# In-Channels.net
KiCad netlist of a schematic drawn in Altium Designer
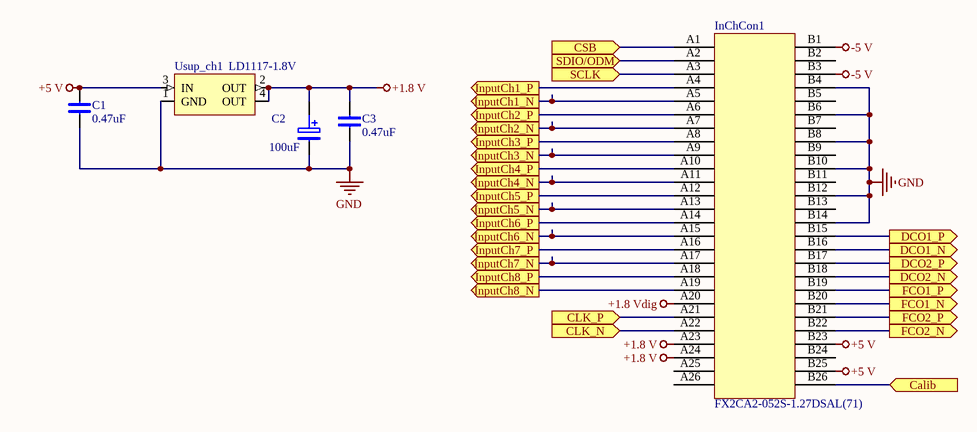
[diagram p0: In-Channels.SchDoc]

(export (version "E")
  (design (tool "Eeschema 10.0.6"))
  (components
    (comp (ref "C1") (value "0.47uF") (footprint "chip0603") (libsource (lib "*") (part "C")))
    (comp (ref "C2") (value "100uF") (footprint "CEL-SMD300") (libsource (lib "*") (part "C POL")))
    (comp (ref "C3") (value "0.47uF") (footprint "chip0603") (libsource (lib "*") (part "C")))
    (comp (ref "InChCon1")
      (value "FX2CA2-052S-1.27DSAL(71)")
      (footprint "FX2CA2-052S-1.27DSAL(71)")
      (libsource (lib "vDevice") (part "FX2CA2-052S-1.27DSAL(71)"))
    )
    (comp (ref "Usup_ch1")
      (value "LD1117-1.8V")
      (footprint "TO-252")
      (libsource (lib "vAnalog") (part "NCP1117-3.3V"))
    )
  )
  (nets
    (net (code "1") (name "+1.8 V") (class "Default")
      (node (ref "C2") (pin "+") (pinfunction "+_+") (pintype "passive"))
      (node (ref "C3") (pin "1") (pinfunction "1_1") (pintype "passive"))
      (node (ref "InChCon1") (pin "A23") (pinfunction "A23_A23") (pintype "passive"))
      (node (ref "InChCon1") (pin "A24") (pinfunction "A24_A24") (pintype "passive"))
      (node (ref "Usup_ch1") (pin "2") (pinfunction "OUT_2") (pintype "output"))
      (node (ref "Usup_ch1") (pin "4") (pinfunction "OUT_4") (pintype "passive"))
    )
    (net (code "2") (name "+1.8 Vdig") (class "Default")
      (node (ref "InChCon1") (pin "A20") (pinfunction "20_A20") (pintype "passive"))
    )
    (net (code "3") (name "+5 V") (class "Default")
      (node (ref "C1") (pin "1") (pinfunction "1_1") (pintype "passive"))
      (node (ref "InChCon1") (pin "B23") (pinfunction "B23_B23") (pintype "passive"))
      (node (ref "InChCon1") (pin "B25") (pinfunction "B25_B25") (pintype "passive"))
      (node (ref "Usup_ch1") (pin "3") (pinfunction "IN_3") (pintype "input"))
    )
    (net (code "4") (name "-5 V") (class "Default")
      (node (ref "InChCon1") (pin "B1") (pinfunction "1_B1") (pintype "passive"))
      (node (ref "InChCon1") (pin "B3") (pinfunction "3_B3") (pintype "passive"))
    )
    (net (code "5") (name "/CLK_N") (class "Default")
      (node (ref "InChCon1") (pin "A22") (pinfunction "A22_A22") (pintype "passive"))
    )
    (net (code "6") (name "/CLK_P") (class "Default")
      (node (ref "InChCon1") (pin "A21") (pinfunction "A21_A21") (pintype "passive"))
    )
    (net (code "7") (name "/CSB") (class "Default")
      (node (ref "InChCon1") (pin "A1") (pinfunction "1_A1") (pintype "passive"))
    )
    (net (code "8") (name "/Calib") (class "Default")
      (node (ref "InChCon1") (pin "B26") (pinfunction "B26_B26") (pintype "passive"))
    )
    (net (code "9") (name "/DCO1_N") (class "Default")
      (node (ref "InChCon1") (pin "B16") (pinfunction "16_B16") (pintype "passive"))
    )
    (net (code "10") (name "/DCO1_P") (class "Default")
      (node (ref "InChCon1") (pin "B15") (pinfunction "15_B15") (pintype "passive"))
    )
    (net (code "11") (name "/DCO2_N") (class "Default")
      (node (ref "InChCon1") (pin "B18") (pinfunction "18_B18") (pintype "passive"))
    )
    (net (code "12") (name "/DCO2_P") (class "Default")
      (node (ref "InChCon1") (pin "B17") (pinfunction "17_B17") (pintype "passive"))
    )
    (net (code "13") (name "/FCO1_N") (class "Default")
      (node (ref "InChCon1") (pin "B20") (pinfunction "20_B20") (pintype "passive"))
    )
    (net (code "14") (name "/FCO1_P") (class "Default")
      (node (ref "InChCon1") (pin "B19") (pinfunction "19_B19") (pintype "passive"))
    )
    (net (code "15") (name "/FCO2_N") (class "Default")
      (node (ref "InChCon1") (pin "B22") (pinfunction "B22_B22") (pintype "passive"))
    )
    (net (code "16") (name "/FCO2_P") (class "Default")
      (node (ref "InChCon1") (pin "B21") (pinfunction "B21_B21") (pintype "passive"))
    )
    (net (code "17") (name "/InputCh1_N") (class "Default")
      (node (ref "InChCon1") (pin "A5") (pinfunction "5_A5") (pintype "passive"))
    )
    (net (code "18") (name "/InputCh1_P") (class "Default")
      (node (ref "InChCon1") (pin "A4") (pinfunction "4_A4") (pintype "passive"))
    )
    (net (code "19") (name "/InputCh2_N") (class "Default")
      (node (ref "InChCon1") (pin "A7") (pinfunction "7_A7") (pintype "passive"))
    )
    (net (code "20") (name "/InputCh2_P") (class "Default")
      (node (ref "InChCon1") (pin "A6") (pinfunction "6_A6") (pintype "passive"))
    )
    (net (code "21") (name "/InputCh3_N") (class "Default")
      (node (ref "InChCon1") (pin "A9") (pinfunction "9_A9") (pintype "passive"))
    )
    (net (code "22") (name "/InputCh3_P") (class "Default")
      (node (ref "InChCon1") (pin "A8") (pinfunction "8_A8") (pintype "passive"))
    )
    (net (code "23") (name "/InputCh4_N") (class "Default")
      (node (ref "InChCon1") (pin "A11") (pinfunction "11_A11") (pintype "passive"))
    )
    (net (code "24") (name "/InputCh4_P") (class "Default")
      (node (ref "InChCon1") (pin "A10") (pinfunction "10_A10") (pintype "passive"))
    )
    (net (code "25") (name "/InputCh5_N") (class "Default")
      (node (ref "InChCon1") (pin "A13") (pinfunction "13_A13") (pintype "passive"))
    )
    (net (code "26") (name "/InputCh5_P") (class "Default")
      (node (ref "InChCon1") (pin "A12") (pinfunction "12_A12") (pintype "passive"))
    )
    (net (code "27") (name "/InputCh6_N") (class "Default")
      (node (ref "InChCon1") (pin "A15") (pinfunction "15_A15") (pintype "passive"))
    )
    (net (code "28") (name "/InputCh6_P") (class "Default")
      (node (ref "InChCon1") (pin "A14") (pinfunction "14_A14") (pintype "passive"))
    )
    (net (code "29") (name "/InputCh7_N") (class "Default")
      (node (ref "InChCon1") (pin "A17") (pinfunction "17_A17") (pintype "passive"))
    )
    (net (code "30") (name "/InputCh7_P") (class "Default")
      (node (ref "InChCon1") (pin "A16") (pinfunction "16_A16") (pintype "passive"))
    )
    (net (code "31") (name "/InputCh8_N") (class "Default")
      (node (ref "InChCon1") (pin "A19") (pinfunction "19_A19") (pintype "passive"))
    )
    (net (code "32") (name "/InputCh8_P") (class "Default")
      (node (ref "InChCon1") (pin "A18") (pinfunction "18_A18") (pintype "passive"))
    )
    (net (code "33") (name "/SCLK") (class "Default")
      (node (ref "InChCon1") (pin "A3") (pinfunction "3_A3") (pintype "passive"))
    )
    (net (code "34") (name "/SDIO{slash}ODM") (class "Default")
      (node (ref "InChCon1") (pin "A2") (pinfunction "2_A2") (pintype "passive"))
    )
    (net (code "35") (name "GND") (class "Default")
      (node (ref "C1") (pin "2") (pinfunction "2_2") (pintype "passive"))
      (node (ref "C2") (pin "-") (pinfunction "-_-") (pintype "passive"))
      (node (ref "C3") (pin "2") (pinfunction "2_2") (pintype "passive"))
      (node (ref "InChCon1") (pin "B10") (pinfunction "10_B10") (pintype "passive"))
      (node (ref "InChCon1") (pin "B12") (pinfunction "12_B12") (pintype "passive"))
      (node (ref "InChCon1") (pin "B14") (pinfunction "14_B14") (pintype "passive"))
      (node (ref "InChCon1") (pin "B4") (pinfunction "4_B4") (pintype "passive"))
      (node (ref "InChCon1") (pin "B6") (pinfunction "6_B6") (pintype "passive"))
      (node (ref "InChCon1") (pin "B8") (pinfunction "8_B8") (pintype "passive"))
      (node (ref "Usup_ch1") (pin "1") (pinfunction "GND_1") (pintype "power_in"))
    )
    (net (code "36") (name "unconnected-(InChCon1-2-PadB2)") (class "Default")
      (node (ref "InChCon1") (pin "B2") (pinfunction "2_B2") (pintype "passive"))
    )
    (net (code "37") (name "unconnected-(InChCon1-5-PadB5)") (class "Default")
      (node (ref "InChCon1") (pin "B5") (pinfunction "5_B5") (pintype "passive"))
    )
    (net (code "38") (name "unconnected-(InChCon1-7-PadB7)") (class "Default")
      (node (ref "InChCon1") (pin "B7") (pinfunction "7_B7") (pintype "passive"))
    )
    (net (code "39") (name "unconnected-(InChCon1-9-PadB9)") (class "Default")
      (node (ref "InChCon1") (pin "B9") (pinfunction "9_B9") (pintype "passive"))
    )
    (net (code "40") (name "unconnected-(InChCon1-11-PadB11)") (class "Default")
      (node (ref "InChCon1") (pin "B11") (pinfunction "11_B11") (pintype "passive"))
    )
    (net (code "41") (name "unconnected-(InChCon1-13-PadB13)") (class "Default")
      (node (ref "InChCon1") (pin "B13") (pinfunction "13_B13") (pintype "passive"))
    )
    (net (code "42") (name "unconnected-(InChCon1-PadA25)") (class "Default")
      (node (ref "InChCon1") (pin "A25") (pinfunction "A25_A25") (pintype "passive"))
    )
    (net (code "43") (name "unconnected-(InChCon1-PadA26)") (class "Default")
      (node (ref "InChCon1") (pin "A26") (pinfunction "A26_A26") (pintype "passive"))
    )
    (net (code "44") (name "unconnected-(InChCon1-PadB24)") (class "Default")
      (node (ref "InChCon1") (pin "B24") (pinfunction "B24_B24") (pintype "passive"))
    )
  )
)
